# microSD.net
KiCad netlist of a schematic drawn in Altium Designer
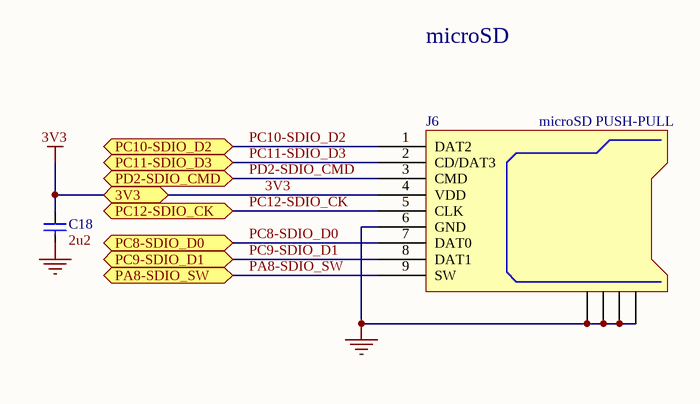
[diagram p0: microSD.SchDoc]

(export (version "E")
  (design (tool "Eeschema 10.0.6"))
  (components
    (comp (ref "C18") (value "2u2") (footprint "SMD0603") (libsource (lib "s_device") (part "Cap")))
    (comp (ref "J6")
      (value "microSD PUSH-PULL")
      (footprint "microSD-1")
      (libsource (lib "s_device") (part "microSD PUSH-PULL"))
    )
  )
  (nets
    (net (code "1") (name "/PA8-SDIO_SW") (class "Default")
      (node (ref "J6") (pin "9") (pinfunction "SW_9") (pintype "passive"))
    )
    (net (code "2") (name "/PC8-SDIO_D0") (class "Default")
      (node (ref "J6") (pin "7") (pinfunction "DAT0_7") (pintype "passive"))
    )
    (net (code "3") (name "/PC9-SDIO_D1") (class "Default")
      (node (ref "J6") (pin "8") (pinfunction "DAT1_8") (pintype "passive"))
    )
    (net (code "4") (name "/PC10-SDIO_D2") (class "Default")
      (node (ref "J6") (pin "1") (pinfunction "DAT2_1") (pintype "passive"))
    )
    (net (code "5") (name "/PC11-SDIO_D3") (class "Default")
      (node (ref "J6") (pin "2") (pinfunction "CD/DAT3_2") (pintype "passive"))
    )
    (net (code "6") (name "/PC12-SDIO_CK") (class "Default")
      (node (ref "J6") (pin "5") (pinfunction "CLK_5") (pintype "passive"))
    )
    (net (code "7") (name "/PD2-SDIO_CMD") (class "Default")
      (node (ref "J6") (pin "3") (pinfunction "CMD_3") (pintype "passive"))
    )
    (net (code "8") (name "3V3") (class "Default")
      (node (ref "C18") (pin "2") (pintype "passive"))
      (node (ref "J6") (pin "4") (pinfunction "VDD_4") (pintype "passive"))
    )
    (net (code "9") (name "GND") (class "Default")
      (node (ref "C18") (pin "1") (pintype "passive"))
      (node (ref "J6") (pin "6") (pinfunction "GND_6") (pintype "passive"))
      (node (ref "J6") (pin "GP1") (pintype "passive"))
      (node (ref "J6") (pin "GP2") (pintype "passive"))
      (node (ref "J6") (pin "GP3") (pintype "passive"))
      (node (ref "J6") (pin "GP4") (pintype "passive"))
    )
  )
)
